# Cyusb3314_Interface.net
KiCad netlist of a schematic drawn in Altium Designer
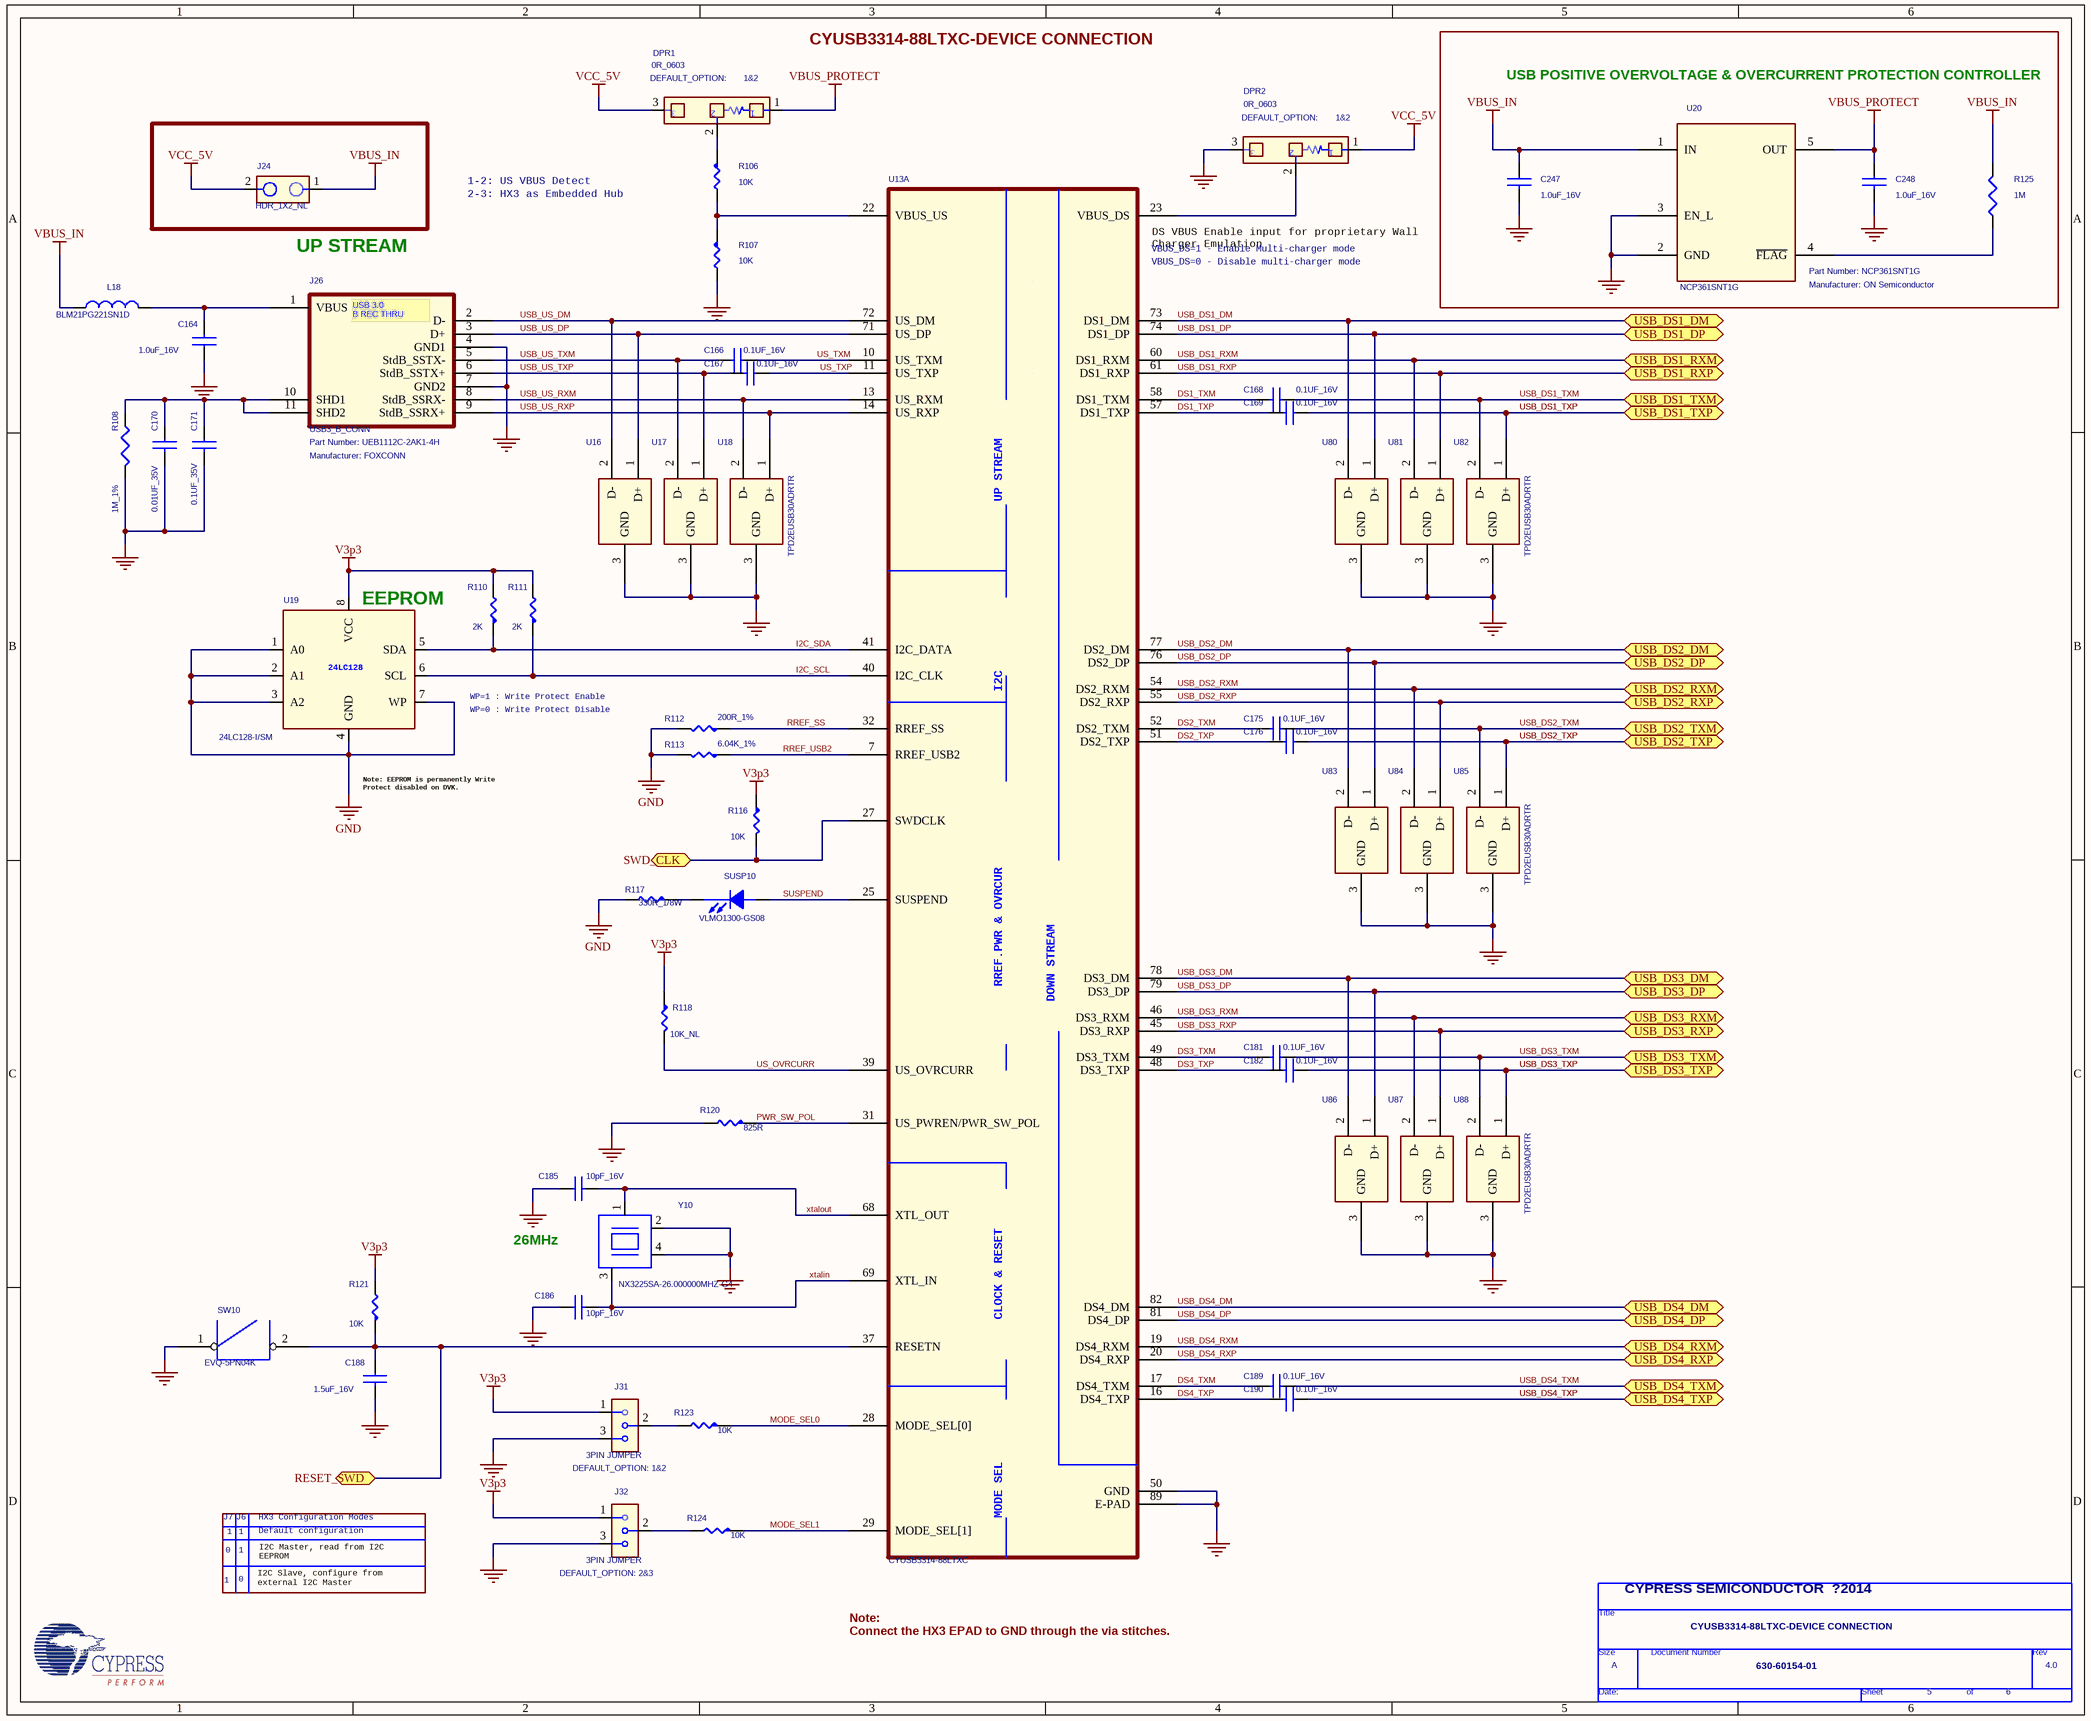
[diagram p0: Cyusb3314_Interface.SchDoc]

(export (version "E")
  (design (tool "Eeschema 10.0.6"))
  (components
    (comp (ref "C164")
      (value "1.0uF_16V")
      (footprint "CAPC1005X56M")
      (libsource (lib "*") (part "CAPACITOR NON-POL"))
    )
    (comp (ref "C166")
      (value "0.1UF_16V")
      (footprint "CAPC1005X56M")
      (libsource (lib "*") (part "CAPACITOR NON-POL"))
    )
    (comp (ref "C167")
      (value "0.1UF_16V")
      (footprint "CAPC1005X56M")
      (libsource (lib "*") (part "CAPACITOR NON-POL"))
    )
    (comp (ref "C168")
      (value "0.1UF_16V")
      (footprint "CAPC1005X56M")
      (libsource (lib "*") (part "CAPACITOR NON-POL"))
    )
    (comp (ref "C169")
      (value "0.1UF_16V")
      (footprint "CAPC1005X56M")
      (libsource (lib "*") (part "CAPACITOR NON-POL"))
    )
    (comp (ref "C170")
      (value "0.01UF_35V")
      (fields (field (name "PART NUMBER") "C1005X7R1V103M050BB"))
      (libsource (lib "*") (part "CAPACITOR NON-POL"))
    )
    (comp (ref "C171")
      (value "0.1UF_35V")
      (fields (field (name "PART NUMBER") "C1005X7R1V104K050BB"))
      (libsource (lib "*") (part "CAPACITOR NON-POL"))
    )
    (comp (ref "C175")
      (value "0.1UF_16V")
      (footprint "CAPC1005X56M")
      (libsource (lib "*") (part "CAPACITOR NON-POL"))
    )
    (comp (ref "C176")
      (value "0.1UF_16V")
      (footprint "CAPC1005X56M")
      (libsource (lib "*") (part "CAPACITOR NON-POL"))
    )
    (comp (ref "C181")
      (value "0.1UF_16V")
      (footprint "CAPC1005X56M")
      (libsource (lib "*") (part "CAPACITOR NON-POL"))
    )
    (comp (ref "C182")
      (value "0.1UF_16V")
      (footprint "CAPC1005X56M")
      (libsource (lib "*") (part "CAPACITOR NON-POL"))
    )
    (comp (ref "C185")
      (value "10pF_16V")
      (footprint "CAPC1608X90M")
      (libsource (lib "*") (part "CAPACITOR NON-POL"))
    )
    (comp (ref "C186")
      (value "10pF_16V")
      (footprint "CAPC1608X90M")
      (libsource (lib "*") (part "CAPACITOR NON-POL"))
    )
    (comp (ref "C188")
      (value "1.5uF_16V")
      (footprint "CAPC1608X90M")
      (description "CAP CER 1.5UF 10V 10% X7R 0805")
      (fields (field (name "MANUFACTURER") "TDK Corporation"))
      (libsource (lib "*") (part "CAPACITOR NON-POL"))
    )
    (comp (ref "C189")
      (value "0.1UF_16V")
      (footprint "CAPC1005X56M")
      (libsource (lib "*") (part "CAPACITOR NON-POL"))
    )
    (comp (ref "C190")
      (value "0.1UF_16V")
      (footprint "CAPC1005X56M")
      (libsource (lib "*") (part "CAPACITOR NON-POL"))
    )
    (comp (ref "C247")
      (value "1.0uF_16V")
      (footprint "CAPC1608X90M")
      (description "CAP - CER, 1uF, 10V, +/-10%, X5R, 0402")
      (libsource (lib "*") (part "CAP"))
    )
    (comp (ref "C248")
      (value "1.0uF_16V")
      (footprint "CAPC1608X90M")
      (description "CAP - CER, 1uF, 10V, +/-10%, X5R, 0402")
      (libsource (lib "*") (part "CAP"))
    )
    (comp (ref "DPR1")
      (value "0R_0603")
      (description "Resistor, 4.7K, 0402, 1/10W, 5%")
      (fields (field (name "MOUNTING STATUS") "1&2") (field (name "PART NUMBER") "ERJ-2GEJ472X"))
      (libsource (lib "*") (part "DPR12_0"))
    )
    (comp (ref "DPR2")
      (value "0R_0603")
      (description "Resistor, 4.7K, 0402, 1/10W, 5%")
      (fields (field (name "MOUNTING STATUS") "1&2") (field (name "PART NUMBER") "ERJ-2GEJ472X"))
      (libsource (lib "*") (part "DPR12_0"))
    )
    (comp (ref "J24")
      (value "HDR_1X2_NL")
      (footprint "SAMTEC_TSW-102-08-G-S")
      (fields (field (name "MANUFACTURER") "Samtec Inc") (field (name "PART NUMBER") "TSW-102-08-G-S"))
      (libsource (lib "*") (part "HEADER_1x2"))
    )
    (comp (ref "J26")
      (value "USB3_B_CONN")
      (footprint "FOXCONN_UEB1112C-2AK1-4H")
      (description "USB 3.0 B Series Right Angle,T/H 9 Pos")
      (fields (field (name "MANUFACTURER") "FOXCONN") (field (name "PART NUMBER") "UEB1112C-2AK1-4H"))
      (libsource (lib "*") (part "UEB1112C-2AK1-4H"))
    )
    (comp (ref "J31")
      (value "3PIN JUMPER")
      (description "CONN HEADER VERT 3POS .100 TIN")
      (fields
        (field (name "PART NUMBER") "3-644456-3")
        (field (name "MANUFACTURER") "Tyco Electronics")
        (field (name "DEFAULT_OPTION") "1&2")
      )
      (libsource (lib "*") (part "3PIN JUM"))
    )
    (comp (ref "J32")
      (value "3PIN JUMPER")
      (description "CONN HEADER VERT 3POS .100 TIN")
      (fields
        (field (name "PART NUMBER") "3-644456-3")
        (field (name "MANUFACTURER") "Tyco Electronics")
        (field (name "DEFAULT_OPTION") "2&3")
      )
      (libsource (lib "*") (part "3PIN JUM"))
    )
    (comp (ref "L18")
      (value "BLM21PG221SN1D")
      (description "FERRITE CHIP 220 OHM 2A 0805")
      (fields (field (name "MANUFACTURER") "Murata"))
      (libsource (lib "*") (part "INDUCTOR"))
    )
    (comp (ref "R106")
      (value "10K")
      (footprint "RESC1005X40M")
      (fields (field (name "MANUFACTURER") "Panasonic") (field (name "PART NUMBER") "ERJ-2GE0R00X"))
      (libsource (lib "*") (part "R_Dup1"))
    )
    (comp (ref "R107")
      (value "10K")
      (footprint "RESC1005X40M")
      (fields (field (name "PART NUMBER") "ERJ-2RKF4990X") (field (name "MANUFACTURER") "Panasonic"))
      (libsource (lib "*") (part "R_Dup1"))
    )
    (comp (ref "R108")
      (value "1M_1%")
      (description "RES 1M OHM 1/10W 1% 0603 SMD")
      (fields (field (name "PART NUMBER") "ERJ-3EKF1004V") (field (name "MANUFACTURER") "Panasonic"))
      (libsource (lib "*") (part "R"))
    )
    (comp (ref "R110")
      (value "2K")
      (footprint "RESC1608X55M")
      (description "RES 2.00K OHM 1/10W 1% 0603 SMD")
      (fields
        (field (name "MANUFACTURER") "Rohm Semiconductor")
        (field (name "PART NUMBER") "MCR03EZPFX2001")
      )
      (libsource (lib "*") (part "R_Dup1"))
    )
    (comp (ref "R111")
      (value "2K")
      (footprint "RESC1608X55M")
      (description "RES 2.00K OHM 1/10W 1% 0603 SMD")
      (fields
        (field (name "PART NUMBER") "MCR03EZPFX2001")
        (field (name "MANUFACTURER") "Rohm Semiconductor")
      )
      (libsource (lib "*") (part "R_Dup1"))
    )
    (comp (ref "R112")
      (value "200R_1%")
      (footprint "RESC1608X50M")
      (description "RES 200 OHM 1% 0603 SMD")
      (fields (field (name "MANUFACTURER") "Stackpole") (field (name "PART NUMBER") "RNCP0603FTD200R"))
      (libsource (lib "*") (part "R_Dup1"))
    )
    (comp (ref "R113")
      (value "6.04K_1%")
      (footprint "RESC1608X55M_A")
      (description "RES 6.04K OHM .25W 1% 0603 SMD")
      (fields (field (name "PART NUMBER") "CRCW06036K04FKEAHP") (field (name "MANUFACTURER") "Vishay Dale"))
      (libsource (lib "*") (part "R_Dup1"))
    )
    (comp (ref "R116")
      (value "10K")
      (footprint "RESC1005X40M")
      (description "RES 10.0K OHM 1/10W 1% 0603 SMD")
      (fields (field (name "MANUFACTURER") "Panasonic - ECG") (field (name "PART NUMBER") "ERJ-3EKF1002V"))
      (libsource (lib "*") (part "R_Dup1"))
    )
    (comp (ref "R117") (value "330R_1/8W") (footprint "RESC1608X50M") (libsource (lib "*") (part "R_Dup1")))
    (comp (ref "R118")
      (value "10K_NL")
      (footprint "RESC1005X40M")
      (description "RES 10.0K OHM 1/10W 1% 0603 SMD")
      (fields (field (name "PART NUMBER") "ERJ-3EKF1002V") (field (name "MANUFACTURER") "Panasonic - ECG"))
      (libsource (lib "*") (part "R_Dup1"))
    )
    (comp (ref "R120")
      (value "825R")
      (footprint "RESC1005X40M")
      (fields (field (name "MANUFACTURER") "Panasonic") (field (name "PART NUMBER") "ERJ-2RKF49.9X"))
      (libsource (lib "*") (part "R_Dup1"))
    )
    (comp (ref "R121")
      (value "10K")
      (footprint "RESC1608X55M")
      (fields (field (name "PART NUMBER") "ERJ-2RKF49.9X") (field (name "MANUFACTURER") "Panasonic"))
      (libsource (lib "*") (part "R_Dup1"))
    )
    (comp (ref "R123")
      (value "10K")
      (footprint "RESC1005X40M")
      (fields (field (name "MANUFACTURER") "Panasonic") (field (name "PART NUMBER") "ERJ-2RKF49.9X"))
      (libsource (lib "*") (part "R_Dup1"))
    )
    (comp (ref "R124")
      (value "10K")
      (footprint "RESC1005X40M")
      (fields (field (name "MANUFACTURER") "Panasonic") (field (name "PART NUMBER") "ERJ-2RKF49.9X"))
      (libsource (lib "*") (part "R_Dup1"))
    )
    (comp (ref "R125")
      (value "1M")
      (description "RES 1.00M OHM 1/10W 1% 0402 SMD")
      (fields (field (name "MANUFACTURER") "Panasonic") (field (name "PART NUMBER") "ERJ-2RKF1004X"))
      (libsource (lib "*") (part "R"))
    )
    (comp (ref "SUSP10") (value "VLMO1300-GS08") (libsource (lib "*") (part "LED")))
    (comp (ref "SW10") (value "EVQ-5PN04K") (libsource (lib "*") (part "B3U1000P")))
    (comp (ref "U13")
      (value "CYUSB3314-88LTXC")
      (footprint "QFN40P1000X1000X100-89M")
      (libsource (lib "*") (part "CYUSB3314-88LTXC_2"))
    )
    (comp (ref "U16")
      (value "TPD2EUSB30ADRTR")
      (footprint "SOTFL35P100X50-3M")
      (libsource (lib "*") (part "TPD2EUSB30ADRTR"))
    )
    (comp (ref "U17")
      (value "TPD2EUSB30ADRTR")
      (footprint "SOTFL35P100X50-3M")
      (libsource (lib "*") (part "TPD2EUSB30ADRTR"))
    )
    (comp (ref "U18")
      (value "TPD2EUSB30ADRTR")
      (footprint "SOTFL35P100X50-3M")
      (libsource (lib "*") (part "TPD2EUSB30ADRTR"))
    )
    (comp (ref "U19")
      (value "24LC128-I/SM")
      (footprint "SOIC127P790X203-8M")
      (description "IC EEPROM 128KBIT 400KHZ 8SOIC")
      (fields (field (name "MANUFACTURER") "Microchip Technology"))
      (libsource (lib "*") (part "24LC128"))
    )
    (comp (ref "U20")
      (value "NCP361SNT1G")
      (footprint "SOP95P275X110-5M")
      (description "IC USB POS OVP/OC_TSOP5")
      (fields (field (name "MANUFACTURER") "ON Semiconductor") (field (name "PART NUMBER") "NCP361SNT1G"))
      (libsource (lib "*") (part "NCP361SNT1G_0"))
    )
    (comp (ref "U80")
      (value "TPD2EUSB30ADRTR")
      (footprint "SOTFL35P100X50-3M")
      (libsource (lib "*") (part "TPD2EUSB30ADRTR"))
    )
    (comp (ref "U81")
      (value "TPD2EUSB30ADRTR")
      (footprint "SOTFL35P100X50-3M")
      (libsource (lib "*") (part "TPD2EUSB30ADRTR"))
    )
    (comp (ref "U82")
      (value "TPD2EUSB30ADRTR")
      (footprint "SOTFL35P100X50-3M")
      (libsource (lib "*") (part "TPD2EUSB30ADRTR"))
    )
    (comp (ref "U83")
      (value "TPD2EUSB30ADRTR")
      (footprint "SOTFL35P100X50-3M")
      (libsource (lib "*") (part "TPD2EUSB30ADRTR"))
    )
    (comp (ref "U84")
      (value "TPD2EUSB30ADRTR")
      (footprint "SOTFL35P100X50-3M")
      (libsource (lib "*") (part "TPD2EUSB30ADRTR"))
    )
    (comp (ref "U85")
      (value "TPD2EUSB30ADRTR")
      (footprint "SOTFL35P100X50-3M")
      (libsource (lib "*") (part "TPD2EUSB30ADRTR"))
    )
    (comp (ref "U86")
      (value "TPD2EUSB30ADRTR")
      (footprint "SOTFL35P100X50-3M")
      (libsource (lib "*") (part "TPD2EUSB30ADRTR"))
    )
    (comp (ref "U87")
      (value "TPD2EUSB30ADRTR")
      (footprint "SOTFL35P100X50-3M")
      (libsource (lib "*") (part "TPD2EUSB30ADRTR"))
    )
    (comp (ref "U88")
      (value "TPD2EUSB30ADRTR")
      (footprint "SOTFL35P100X50-3M")
      (libsource (lib "*") (part "TPD2EUSB30ADRTR"))
    )
    (comp (ref "Y10")
      (value "NX3225SA-26.000000MHZ-G4")
      (fields (field (name "MANUFACTURER") "NDK"))
      (libsource (lib "*") (part "CRYSTAL_1"))
    )
  )
  (nets
    (net (code "1") (name "/DS1_TXM") (class "Default")
      (node (ref "C168") (pin "2") (pinfunction "2_2") (pintype "passive"))
      (node (ref "U13") (pin "58") (pinfunction "DS1_TXM_58") (pintype "passive"))
    )
    (net (code "2") (name "/DS1_TXP") (class "Default")
      (node (ref "C169") (pin "2") (pinfunction "2_2") (pintype "passive"))
      (node (ref "U13") (pin "57") (pinfunction "DS1_TXP_57") (pintype "passive"))
    )
    (net (code "3") (name "/DS2_TXM") (class "Default")
      (node (ref "C175") (pin "2") (pinfunction "2_2") (pintype "passive"))
      (node (ref "U13") (pin "52") (pinfunction "DS2_TXM_52") (pintype "passive"))
    )
    (net (code "4") (name "/DS2_TXP") (class "Default")
      (node (ref "C176") (pin "2") (pinfunction "2_2") (pintype "passive"))
      (node (ref "U13") (pin "51") (pinfunction "DS2_TXP_51") (pintype "passive"))
    )
    (net (code "5") (name "/DS3_TXM") (class "Default")
      (node (ref "C181") (pin "2") (pinfunction "2_2") (pintype "passive"))
      (node (ref "U13") (pin "49") (pinfunction "DS3_TXM_49") (pintype "passive"))
    )
    (net (code "6") (name "/DS3_TXP") (class "Default")
      (node (ref "C182") (pin "2") (pinfunction "2_2") (pintype "passive"))
      (node (ref "U13") (pin "48") (pinfunction "DS3_TXP_48") (pintype "passive"))
    )
    (net (code "7") (name "/DS4_TXM") (class "Default")
      (node (ref "C189") (pin "2") (pinfunction "2_2") (pintype "passive"))
      (node (ref "U13") (pin "17") (pinfunction "DS4_TXM_17") (pintype "passive"))
    )
    (net (code "8") (name "/DS4_TXP") (class "Default")
      (node (ref "C190") (pin "2") (pinfunction "2_2") (pintype "passive"))
      (node (ref "U13") (pin "16") (pinfunction "DS4_TXP_16") (pintype "passive"))
    )
    (net (code "9") (name "/I2C_SCL") (class "Default")
      (node (ref "R111") (pin "1") (pinfunction "1_1") (pintype "passive"))
      (node (ref "U13") (pin "40") (pinfunction "I2C_CLK_40") (pintype "passive"))
      (node (ref "U19") (pin "6") (pinfunction "SCL_6") (pintype "passive"))
    )
    (net (code "10") (name "/I2C_SDA") (class "Default")
      (node (ref "R110") (pin "1") (pinfunction "1_1") (pintype "passive"))
      (node (ref "U13") (pin "41") (pinfunction "I2C_DATA_41") (pintype "passive"))
      (node (ref "U19") (pin "5") (pinfunction "SDA_5") (pintype "passive"))
    )
    (net (code "11") (name "/MODE_SEL0") (class "Default")
      (node (ref "R123") (pin "1") (pinfunction "1_1") (pintype "passive"))
      (node (ref "U13") (pin "28") (pinfunction "MODE_SEL[0]_28") (pintype "passive"))
    )
    (net (code "12") (name "/MODE_SEL1") (class "Default")
      (node (ref "R124") (pin "1") (pinfunction "1_1") (pintype "passive"))
      (node (ref "U13") (pin "29") (pinfunction "MODE_SEL[1]_29") (pintype "passive"))
    )
    (net (code "13") (name "/PWR_SW_POL") (class "Default")
      (node (ref "R120") (pin "1") (pinfunction "1_1") (pintype "passive"))
      (node (ref "U13") (pin "31") (pinfunction "US_PWREN/PWR_SW_POL_31") (pintype "passive"))
    )
    (net (code "14") (name "/RESET_SWD") (class "Default")
      (node (ref "C188") (pin "1") (pinfunction "1_1") (pintype "passive"))
      (node (ref "R121") (pin "1") (pinfunction "1_1") (pintype "passive"))
      (node (ref "SW10") (pin "2") (pinfunction "2_2") (pintype "passive"))
      (node (ref "U13") (pin "37") (pinfunction "RESETN_37") (pintype "passive"))
    )
    (net (code "15") (name "/RREF_SS") (class "Default")
      (node (ref "R112") (pin "1") (pinfunction "1_1") (pintype "passive"))
      (node (ref "U13") (pin "32") (pinfunction "RREF_SS_32") (pintype "passive"))
    )
    (net (code "16") (name "/RREF_USB2") (class "Default")
      (node (ref "R113") (pin "1") (pinfunction "1_1") (pintype "passive"))
      (node (ref "U13") (pin "7") (pinfunction "RREF_USB2_7") (pintype "passive"))
    )
    (net (code "17") (name "/SUSPEND") (class "Default")
      (node (ref "SUSP10") (pin "1") (pinfunction "ANODE_1") (pintype "passive"))
      (node (ref "U13") (pin "25") (pinfunction "SUSPEND_25") (pintype "passive"))
    )
    (net (code "18") (name "/SWD_CLK") (class "Default")
      (node (ref "R116") (pin "2") (pinfunction "2_2") (pintype "passive"))
      (node (ref "U13") (pin "27") (pinfunction "SWDCLK_27") (pintype "passive"))
    )
    (net (code "19") (name "/USB_DS1_DM") (class "Default")
      (node (ref "U13") (pin "73") (pinfunction "DS1_DM_73") (pintype "passive"))
      (node (ref "U80") (pin "2") (pinfunction "D-_2") (pintype "passive"))
    )
    (net (code "20") (name "/USB_DS1_DP") (class "Default")
      (node (ref "U13") (pin "74") (pinfunction "DS1_DP_74") (pintype "passive"))
      (node (ref "U80") (pin "1") (pinfunction "D+_1") (pintype "passive"))
    )
    (net (code "21") (name "/USB_DS1_RXM") (class "Default")
      (node (ref "U13") (pin "60") (pinfunction "DS1_RXM_60") (pintype "passive"))
      (node (ref "U81") (pin "2") (pinfunction "D-_2") (pintype "passive"))
    )
    (net (code "22") (name "/USB_DS1_RXP") (class "Default")
      (node (ref "U13") (pin "61") (pinfunction "DS1_RXP_61") (pintype "passive"))
      (node (ref "U81") (pin "1") (pinfunction "D+_1") (pintype "passive"))
    )
    (net (code "23") (name "/USB_DS1_TXM") (class "Default")
      (node (ref "C168") (pin "1") (pinfunction "1_1") (pintype "passive"))
      (node (ref "U82") (pin "2") (pinfunction "D-_2") (pintype "passive"))
    )
    (net (code "24") (name "/USB_DS1_TXP") (class "Default")
      (node (ref "C169") (pin "1") (pinfunction "1_1") (pintype "passive"))
      (node (ref "U82") (pin "1") (pinfunction "D+_1") (pintype "passive"))
    )
    (net (code "25") (name "/USB_DS2_DM") (class "Default")
      (node (ref "U13") (pin "77") (pinfunction "DS2_DM_77") (pintype "passive"))
      (node (ref "U83") (pin "2") (pinfunction "D-_2") (pintype "passive"))
    )
    (net (code "26") (name "/USB_DS2_DP") (class "Default")
      (node (ref "U13") (pin "76") (pinfunction "DS2_DP_76") (pintype "passive"))
      (node (ref "U83") (pin "1") (pinfunction "D+_1") (pintype "passive"))
    )
    (net (code "27") (name "/USB_DS2_RXM") (class "Default")
      (node (ref "U13") (pin "54") (pinfunction "DS2_RXM_54") (pintype "passive"))
      (node (ref "U84") (pin "2") (pinfunction "D-_2") (pintype "passive"))
    )
    (net (code "28") (name "/USB_DS2_RXP") (class "Default")
      (node (ref "U13") (pin "55") (pinfunction "DS2_RXP_55") (pintype "passive"))
      (node (ref "U84") (pin "1") (pinfunction "D+_1") (pintype "passive"))
    )
    (net (code "29") (name "/USB_DS2_TXM") (class "Default")
      (node (ref "C175") (pin "1") (pinfunction "1_1") (pintype "passive"))
      (node (ref "U85") (pin "2") (pinfunction "D-_2") (pintype "passive"))
    )
    (net (code "30") (name "/USB_DS2_TXP") (class "Default")
      (node (ref "C176") (pin "1") (pinfunction "1_1") (pintype "passive"))
      (node (ref "U85") (pin "1") (pinfunction "D+_1") (pintype "passive"))
    )
    (net (code "31") (name "/USB_DS3_DM") (class "Default")
      (node (ref "U13") (pin "78") (pinfunction "DS3_DM_78") (pintype "passive"))
      (node (ref "U86") (pin "2") (pinfunction "D-_2") (pintype "passive"))
    )
    (net (code "32") (name "/USB_DS3_DP") (class "Default")
      (node (ref "U13") (pin "79") (pinfunction "DS3_DP_79") (pintype "passive"))
      (node (ref "U86") (pin "1") (pinfunction "D+_1") (pintype "passive"))
    )
    (net (code "33") (name "/USB_DS3_RXM") (class "Default")
      (node (ref "U13") (pin "46") (pinfunction "DS3_RXM_46") (pintype "passive"))
      (node (ref "U87") (pin "2") (pinfunction "D-_2") (pintype "passive"))
    )
    (net (code "34") (name "/USB_DS3_RXP") (class "Default")
      (node (ref "U13") (pin "45") (pinfunction "DS3_RXP_45") (pintype "passive"))
      (node (ref "U87") (pin "1") (pinfunction "D+_1") (pintype "passive"))
    )
    (net (code "35") (name "/USB_DS3_TXM") (class "Default")
      (node (ref "C181") (pin "1") (pinfunction "1_1") (pintype "passive"))
      (node (ref "U88") (pin "2") (pinfunction "D-_2") (pintype "passive"))
    )
    (net (code "36") (name "/USB_DS3_TXP") (class "Default")
      (node (ref "C182") (pin "1") (pinfunction "1_1") (pintype "passive"))
      (node (ref "U88") (pin "1") (pinfunction "D+_1") (pintype "passive"))
    )
    (net (code "37") (name "/USB_DS4_DM") (class "Default")
      (node (ref "U13") (pin "82") (pinfunction "DS4_DM_82") (pintype "passive"))
    )
    (net (code "38") (name "/USB_DS4_DP") (class "Default")
      (node (ref "U13") (pin "81") (pinfunction "DS4_DP_81") (pintype "passive"))
    )
    (net (code "39") (name "/USB_DS4_RXM") (class "Default")
      (node (ref "U13") (pin "19") (pinfunction "DS4_RXM_19") (pintype "passive"))
    )
    (net (code "40") (name "/USB_DS4_RXP") (class "Default")
      (node (ref "U13") (pin "20") (pinfunction "DS4_RXP_20") (pintype "passive"))
    )
    (net (code "41") (name "/USB_DS4_TXM") (class "Default")
      (node (ref "C189") (pin "1") (pinfunction "1_1") (pintype "passive"))
    )
    (net (code "42") (name "/USB_DS4_TXP") (class "Default")
      (node (ref "C190") (pin "1") (pinfunction "1_1") (pintype "passive"))
    )
    (net (code "43") (name "/USB_US_DM") (class "Default")
      (node (ref "J26") (pin "2") (pinfunction "D-_2") (pintype "passive"))
      (node (ref "U13") (pin "72") (pinfunction "US_DM_72") (pintype "passive"))
      (node (ref "U16") (pin "2") (pinfunction "D-_2") (pintype "passive"))
    )
    (net (code "44") (name "/USB_US_DP") (class "Default")
      (node (ref "J26") (pin "3") (pinfunction "D+_3") (pintype "passive"))
      (node (ref "U13") (pin "71") (pinfunction "US_DP_71") (pintype "passive"))
      (node (ref "U16") (pin "1") (pinfunction "D+_1") (pintype "passive"))
    )
    (net (code "45") (name "/USB_US_RXM") (class "Default")
      (node (ref "J26") (pin "8") (pinfunction "StdB_SSRX-_8") (pintype "passive"))
      (node (ref "U13") (pin "13") (pinfunction "US_RXM_13") (pintype "passive"))
      (node (ref "U18") (pin "2") (pinfunction "D-_2") (pintype "passive"))
    )
    (net (code "46") (name "/USB_US_RXP") (class "Default")
      (node (ref "J26") (pin "9") (pinfunction "StdB_SSRX+_9") (pintype "passive"))
      (node (ref "U13") (pin "14") (pinfunction "US_RXP_14") (pintype "passive"))
      (node (ref "U18") (pin "1") (pinfunction "D+_1") (pintype "passive"))
    )
    (net (code "47") (name "/USB_US_TXM") (class "Default")
      (node (ref "C166") (pin "2") (pinfunction "2_2") (pintype "passive"))
      (node (ref "J26") (pin "5") (pinfunction "StdB_SSTX-_5") (pintype "passive"))
      (node (ref "U17") (pin "2") (pinfunction "D-_2") (pintype "passive"))
    )
    (net (code "48") (name "/USB_US_TXP") (class "Default")
      (node (ref "C167") (pin "2") (pinfunction "2_2") (pintype "passive"))
      (node (ref "J26") (pin "6") (pinfunction "StdB_SSTX+_6") (pintype "passive"))
      (node (ref "U17") (pin "1") (pinfunction "D+_1") (pintype "passive"))
    )
    (net (code "49") (name "/US_OVRCURR") (class "Default")
      (node (ref "R118") (pin "2") (pinfunction "2_2") (pintype "passive"))
      (node (ref "U13") (pin "39") (pinfunction "US_OVRCURR_39") (pintype "passive"))
    )
    (net (code "50") (name "/US_TXM") (class "Default")
      (node (ref "C166") (pin "1") (pinfunction "1_1") (pintype "passive"))
      (node (ref "U13") (pin "10") (pinfunction "US_TXM_10") (pintype "passive"))
    )
    (net (code "51") (name "/US_TXP") (class "Default")
      (node (ref "C167") (pin "1") (pinfunction "1_1") (pintype "passive"))
      (node (ref "U13") (pin "11") (pinfunction "US_TXP_11") (pintype "passive"))
    )
    (net (code "52") (name "/xtalin") (class "Default")
      (node (ref "C186") (pin "2") (pinfunction "2_2") (pintype "passive"))
      (node (ref "U13") (pin "69") (pinfunction "XTL_IN_69") (pintype "passive"))
      (node (ref "Y10") (pin "3") (pinfunction "3_3") (pintype "passive"))
    )
    (net (code "53") (name "/xtalout") (class "Default")
      (node (ref "C185") (pin "2") (pinfunction "2_2") (pintype "passive"))
      (node (ref "U13") (pin "68") (pinfunction "XTL_OUT_68") (pintype "passive"))
      (node (ref "Y10") (pin "1") (pinfunction "1_1") (pintype "passive"))
    )
    (net (code "54") (name "GND") (class "Default")
      (node (ref "C164") (pin "1") (pinfunction "1_1") (pintype "passive"))
      (node (ref "C170") (pin "2") (pinfunction "2_2") (pintype "passive"))
      (node (ref "C171") (pin "2") (pinfunction "2_2") (pintype "passive"))
      (node (ref "C185") (pin "1") (pinfunction "1_1") (pintype "passive"))
      (node (ref "C186") (pin "1") (pinfunction "1_1") (pintype "passive"))
      (node (ref "C188") (pin "2") (pinfunction "2_2") (pintype "passive"))
      (node (ref "C247") (pin "2") (pinfunction "2_2") (pintype "passive"))
      (node (ref "C248") (pin "2") (pinfunction "2_2") (pintype "passive"))
      (node (ref "DPR2") (pin "3") (pinfunction "3_3") (pintype "passive"))
      (node (ref "J26") (pin "4") (pinfunction "GND1_4") (pintype "passive"))
      (node (ref "J26") (pin "7") (pinfunction "GND2_7") (pintype "passive"))
      (node (ref "J31") (pin "3") (pinfunction "3_3") (pintype "passive"))
      (node (ref "J32") (pin "3") (pinfunction "3_3") (pintype "passive"))
      (node (ref "R107") (pin "2") (pinfunction "2_2") (pintype "passive"))
      (node (ref "R108") (pin "2") (pinfunction "2_2") (pintype "passive"))
      (node (ref "R112") (pin "2") (pinfunction "2_2") (pintype "passive"))
      (node (ref "R113") (pin "2") (pinfunction "2_2") (pintype "passive"))
      (node (ref "R117") (pin "2") (pinfunction "2_2") (pintype "passive"))
      (node (ref "R120") (pin "2") (pinfunction "2_2") (pintype "passive"))
      (node (ref "SW10") (pin "1") (pinfunction "1_1") (pintype "passive"))
      (node (ref "U13") (pin "50") (pinfunction "GND_50") (pintype "passive"))
      (node (ref "U13") (pin "89") (pinfunction "E-PAD_89") (pintype "passive"))
      (node (ref "U16") (pin "3") (pinfunction "GND_3") (pintype "passive"))
      (node (ref "U17") (pin "3") (pinfunction "GND_3") (pintype "passive"))
      (node (ref "U18") (pin "3") (pinfunction "GND_3") (pintype "passive"))
      (node (ref "U19") (pin "1") (pinfunction "A0_1") (pintype "passive"))
      (node (ref "U19") (pin "2") (pinfunction "A1_2") (pintype "passive"))
      (node (ref "U19") (pin "3") (pinfunction "A2_3") (pintype "passive"))
      (node (ref "U19") (pin "4") (pinfunction "GND_4") (pintype "passive"))
      (node (ref "U19") (pin "7") (pinfunction "WP_7") (pintype "passive"))
      (node (ref "U20") (pin "2") (pinfunction "GND_2") (pintype "passive"))
      (node (ref "U20") (pin "3") (pinfunction "EN_L_3") (pintype "passive"))
      (node (ref "U80") (pin "3") (pinfunction "GND_3") (pintype "passive"))
      (node (ref "U81") (pin "3") (pinfunction "GND_3") (pintype "passive"))
      (node (ref "U82") (pin "3") (pinfunction "GND_3") (pintype "passive"))
      (node (ref "U83") (pin "3") (pinfunction "GND_3") (pintype "passive"))
      (node (ref "U84") (pin "3") (pinfunction "GND_3") (pintype "passive"))
      (node (ref "U85") (pin "3") (pinfunction "GND_3") (pintype "passive"))
      (node (ref "U86") (pin "3") (pinfunction "GND_3") (pintype "passive"))
      (node (ref "U87") (pin "3") (pinfunction "GND_3") (pintype "passive"))
      (node (ref "U88") (pin "3") (pinfunction "GND_3") (pintype "passive"))
      (node (ref "Y10") (pin "2") (pinfunction "2_2") (pintype "passive"))
      (node (ref "Y10") (pin "4") (pinfunction "4_4") (pintype "passive"))
    )
    (net (code "55") (name "Net-(DPR1-Pad2)") (class "Default")
      (node (ref "DPR1") (pin "2") (pinfunction "2_2") (pintype "passive"))
      (node (ref "R106") (pin "1") (pinfunction "1_1") (pintype "passive"))
    )
    (net (code "56") (name "Net-(J26-SHD1)") (class "Default")
      (node (ref "C170") (pin "1") (pinfunction "1_1") (pintype "passive"))
      (node (ref "C171") (pin "1") (pinfunction "1_1") (pintype "passive"))
      (node (ref "J26") (pin "10") (pinfunction "SHD1_10") (pintype "passive"))
      (node (ref "J26") (pin "11") (pinfunction "SHD2_11") (pintype "passive"))
      (node (ref "R108") (pin "1") (pinfunction "1_1") (pintype "passive"))
    )
    (net (code "57") (name "Net-(J26-VBUS)") (class "Default")
      (node (ref "C164") (pin "2") (pinfunction "2_2") (pintype "passive"))
      (node (ref "J26") (pin "1") (pinfunction "VBUS_1") (pintype "passive"))
      (node (ref "L18") (pin "2") (pinfunction "2_2") (pintype "passive"))
    )
    (net (code "58") (name "Net-(J31-Pad2)") (class "Default")
      (node (ref "J31") (pin "2") (pinfunction "2_2") (pintype "passive"))
      (node (ref "R123") (pin "2") (pinfunction "2_2") (pintype "passive"))
    )
    (net (code "59") (name "Net-(J32-Pad2)") (class "Default")
      (node (ref "J32") (pin "2") (pinfunction "2_2") (pintype "passive"))
      (node (ref "R124") (pin "2") (pinfunction "2_2") (pintype "passive"))
    )
    (net (code "60") (name "Net-(SUSP10-CATHODE)") (class "Default")
      (node (ref "R117") (pin "1") (pinfunction "1_1") (pintype "passive"))
      (node (ref "SUSP10") (pin "2") (pinfunction "CATHODE_2") (pintype "passive"))
    )
    (net (code "61") (name "Net-(U13A-VBUS_DS)") (class "Default")
      (node (ref "DPR2") (pin "2") (pinfunction "2_2") (pintype "passive"))
      (node (ref "U13") (pin "23") (pinfunction "VBUS_DS_23") (pintype "passive"))
    )
    (net (code "62") (name "Net-(U13A-VBUS_US)") (class "Default")
      (node (ref "R106") (pin "2") (pinfunction "2_2") (pintype "passive"))
      (node (ref "R107") (pin "1") (pinfunction "1_1") (pintype "passive"))
      (node (ref "U13") (pin "22") (pinfunction "VBUS_US_22") (pintype "passive"))
    )
    (net (code "63") (name "Net-(U20-~{FLAG})") (class "Default")
      (node (ref "R125") (pin "1") (pinfunction "1_1") (pintype "passive"))
      (node (ref "U20") (pin "4") (pinfunction "~{FLAG}_4") (pintype "passive"))
    )
    (net (code "64") (name "V3p3") (class "Default")
      (node (ref "J31") (pin "1") (pinfunction "1_1") (pintype "passive"))
      (node (ref "J32") (pin "1") (pinfunction "1_1") (pintype "passive"))
      (node (ref "R110") (pin "2") (pinfunction "2_2") (pintype "passive"))
      (node (ref "R111") (pin "2") (pinfunction "2_2") (pintype "passive"))
      (node (ref "R116") (pin "1") (pinfunction "1_1") (pintype "passive"))
      (node (ref "R118") (pin "1") (pinfunction "1_1") (pintype "passive"))
      (node (ref "R121") (pin "2") (pinfunction "2_2") (pintype "passive"))
      (node (ref "U19") (pin "8") (pinfunction "VCC_8") (pintype "passive"))
    )
    (net (code "65") (name "VBUS_IN") (class "Default")
      (node (ref "C247") (pin "1") (pinfunction "1_1") (pintype "passive"))
      (node (ref "J24") (pin "1") (pinfunction "1_1") (pintype "passive"))
      (node (ref "L18") (pin "1") (pinfunction "1_1") (pintype "passive"))
      (node (ref "R125") (pin "2") (pinfunction "2_2") (pintype "passive"))
      (node (ref "U20") (pin "1") (pinfunction "IN_1") (pintype "passive"))
    )
    (net (code "66") (name "VBUS_PROTECT") (class "Default")
      (node (ref "C248") (pin "1") (pinfunction "1_1") (pintype "passive"))
      (node (ref "DPR1") (pin "1") (pinfunction "1_1") (pintype "passive"))
      (node (ref "U20") (pin "5") (pinfunction "OUT_5") (pintype "passive"))
    )
    (net (code "67") (name "VCC_5V") (class "Default")
      (node (ref "DPR1") (pin "3") (pinfunction "3_3") (pintype "passive"))
      (node (ref "DPR2") (pin "1") (pinfunction "1_1") (pintype "passive"))
      (node (ref "J24") (pin "2") (pinfunction "2_2") (pintype "passive"))
    )
  )
)
